# Dandanator_CPC_MX4_v1_2_Rwd.net
KiCad netlist of a schematic drawn in EAGLE
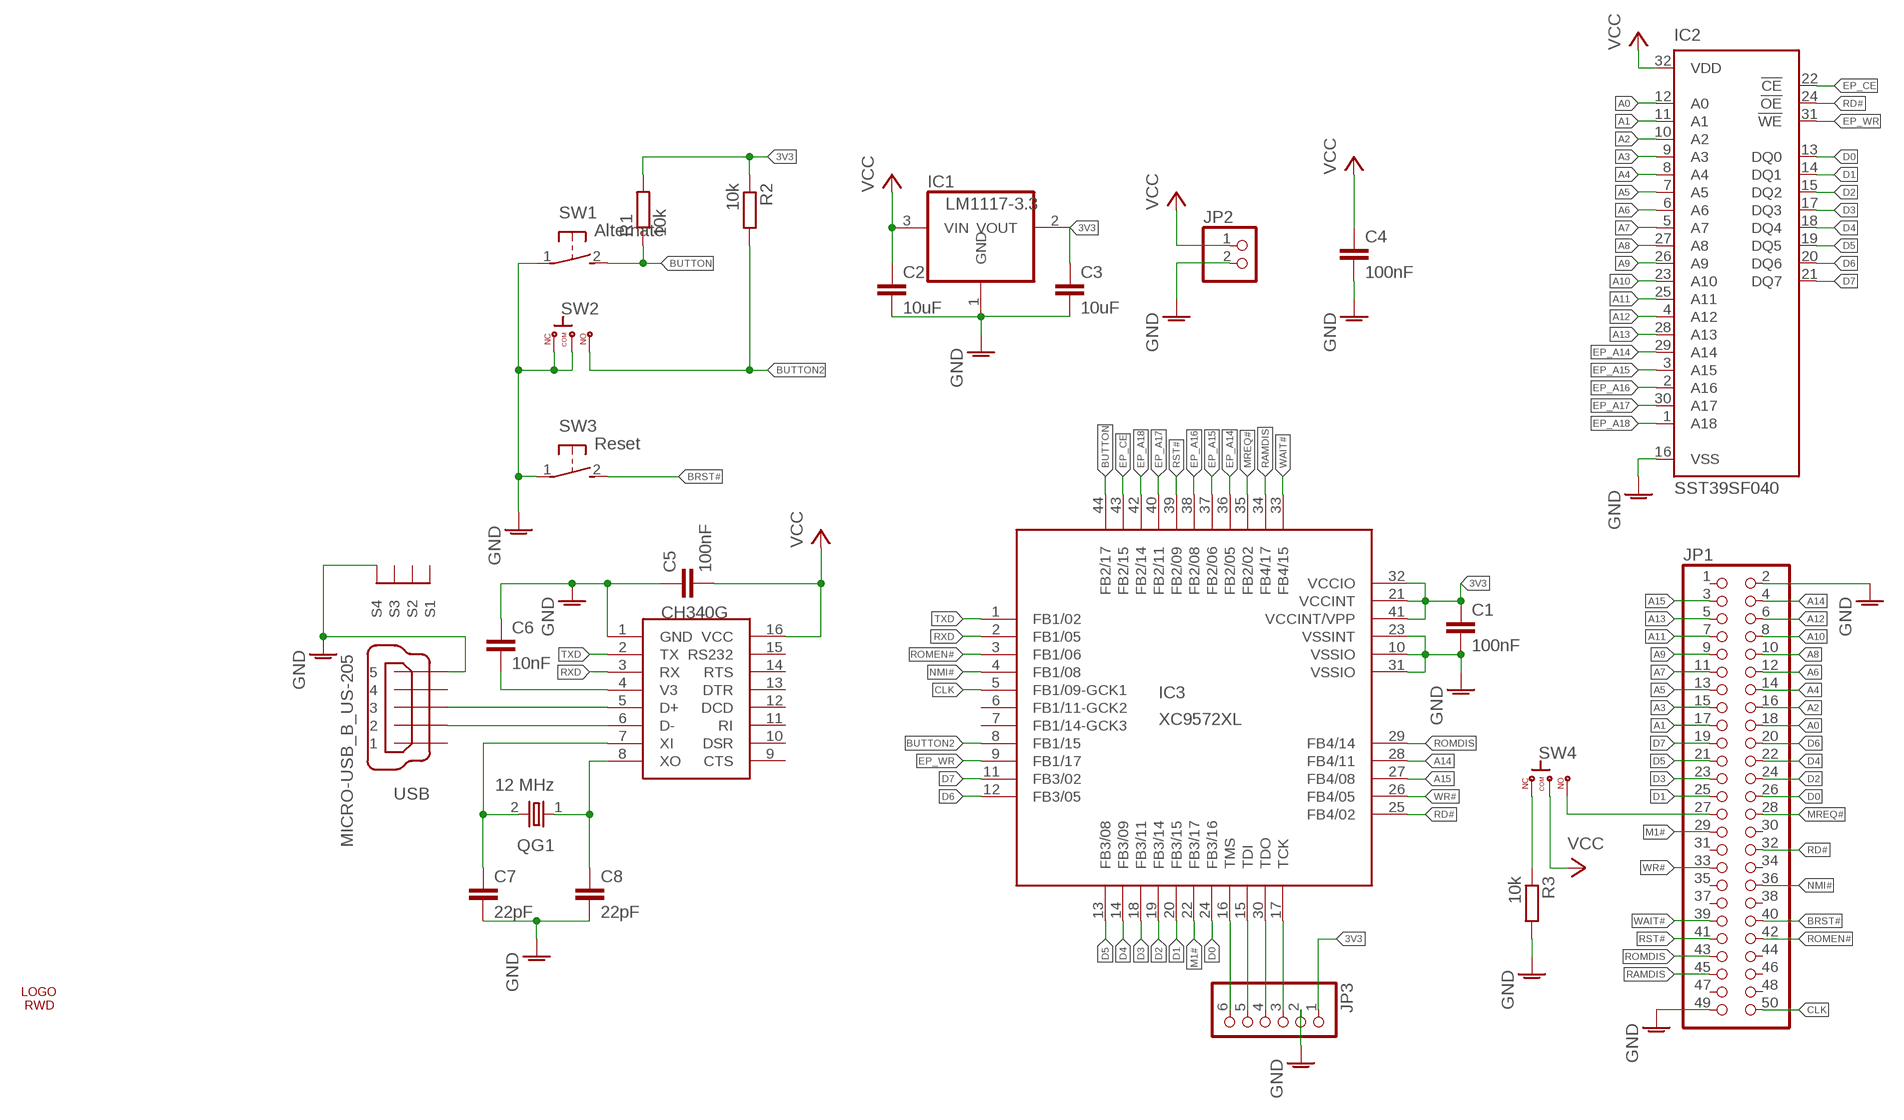
[diagram p0: schematic, sheet 1]

(export (version "E")
  (design (tool "Eeschema 10.0.6"))
  (components
    (comp (ref "C1")
      (value "100nF")
      (footprint "eagle-import:C0805")
      (libsource (lib "eagle-import") (part "C-EUC0805"))
    )
    (comp (ref "C2")
      (value "10uF")
      (footprint "eagle-import:C0805")
      (libsource (lib "eagle-import") (part "C-EUC0805"))
    )
    (comp (ref "C3")
      (value "10uF")
      (footprint "eagle-import:C0805")
      (libsource (lib "eagle-import") (part "C-EUC0805"))
    )
    (comp (ref "C4")
      (value "100nF")
      (footprint "eagle-import:C0805")
      (libsource (lib "eagle-import") (part "C-EUC0805"))
    )
    (comp (ref "C5")
      (value "100nF")
      (footprint "eagle-import:C0805")
      (libsource (lib "eagle-import") (part "C-EUC0805"))
    )
    (comp (ref "C6")
      (value "10nF")
      (footprint "eagle-import:C0805")
      (libsource (lib "eagle-import") (part "C-EUC0805"))
    )
    (comp (ref "C7")
      (value "22pF")
      (footprint "eagle-import:C0805")
      (libsource (lib "eagle-import") (part "C-EUC0805"))
    )
    (comp (ref "C8")
      (value "22pF")
      (footprint "eagle-import:C0805")
      (libsource (lib "eagle-import") (part "C-EUC0805"))
    )
    (comp (ref "CH340G")
      (value "CH340G")
      (footprint "eagle-import:SOIC16")
      (libsource (lib "eagle-import") (part "CH340G"))
    )
    (comp (ref "IC1")
      (value "LM1117-3.3")
      (footprint "eagle-import:SOT223")
      (fields (field (name "MPN") "REG1117"))
      (libsource (lib "eagle-import") (part "REG1117"))
    )
    (comp (ref "IC2")
      (value "SST39SF040")
      (footprint "eagle-import:S32")
      (libsource (lib "eagle-import") (part "MICROCHIP_SST39SF040C"))
    )
    (comp (ref "IC3")
      (value "XC9572XL")
      (footprint "eagle-import:S44")
      (libsource (lib "eagle-import") (part "XC9572XL_44PLCCDIP"))
    )
    (comp (ref "JP1")
      (value "PINHD-2X25")
      (footprint "eagle-import:2X25")
      (libsource (lib "eagle-import") (part "PINHD-2X25"))
    )
    (comp (ref "JP2")
      (value "PINHD-1X2")
      (footprint "eagle-import:1X02")
      (libsource (lib "eagle-import") (part "PINHD-1X2"))
    )
    (comp (ref "JP3")
      (value "PINHD-1X6")
      (footprint "eagle-import:1X06")
      (libsource (lib "eagle-import") (part "PINHD-1X6"))
    )
    (comp (ref "QG1")
      (value "12 MHz")
      (footprint "eagle-import:CRYSTAL_HC49_S")
      (libsource (lib "eagle-import") (part "CRYSTAL_CRYSTALHC49S"))
    )
    (comp (ref "R1")
      (value "10k")
      (footprint "eagle-import:R0805")
      (libsource (lib "eagle-import") (part "R-EU_R0805"))
    )
    (comp (ref "R2")
      (value "10k")
      (footprint "eagle-import:R0805")
      (libsource (lib "eagle-import") (part "R-EU_R0805"))
    )
    (comp (ref "R3")
      (value "10k")
      (footprint "eagle-import:R0805")
      (libsource (lib "eagle-import") (part "R-EU_R0805"))
    )
    (comp (ref "SW1")
      (value "Alternate")
      (footprint "eagle-import:B3F-31XX")
      (fields (field (name "MPN") "B3F-3100"))
      (libsource (lib "eagle-import") (part "31-XX"))
    )
    (comp (ref "SW2")
      (value "Disable")
      (footprint "eagle-import:1P2T-MSK12D19-DIP")
      (libsource (lib "eagle-import") (part "1P2T-MSK12D19"))
    )
    (comp (ref "SW3")
      (value "Reset")
      (footprint "eagle-import:B3F-31XX")
      (fields (field (name "MPN") "B3F-3100"))
      (libsource (lib "eagle-import") (part "31-XX"))
    )
    (comp (ref "SW4")
      (value "ON/OFF")
      (footprint "eagle-import:1P2T-MSK12D19-DIP")
      (libsource (lib "eagle-import") (part "1P2T-MSK12D19"))
    )
    (comp (ref "U$1")
      (value "LOGO7BOTTOM")
      (footprint "eagle-import:LOGO7_SK22")
      (libsource (lib "eagle-import") (part "LOGO7BOTTOM"))
    )
    (comp (ref "USB")
      (value "MICRO-USB_B_US-205")
      (footprint "eagle-import:MICRO-USB_B_US-205_DIP")
      (libsource (lib "eagle-import") (part "MICRO-USB_B_US-205"))
    )
  )
  (nets
    (net (code "1") (name "3V3") (class "Default")
      (node (ref "C1") (pin "1") (pinfunction "1_1") (pintype "passive"))
      (node (ref "C3") (pin "1") (pinfunction "1_1") (pintype "passive"))
      (node (ref "IC1") (pin "2") (pinfunction "VOUT_2") (pintype "output"))
      (node (ref "IC3") (pin "21") (pinfunction "VCCINT_21") (pintype "power_in"))
      (node (ref "IC3") (pin "32") (pinfunction "VCCIO_32") (pintype "power_in"))
      (node (ref "IC3") (pin "41") (pinfunction "VCCINT/VPP_41") (pintype "input"))
      (node (ref "JP3") (pin "1") (pinfunction "1_1") (pintype "passive"))
      (node (ref "R1") (pin "2") (pinfunction "2_2") (pintype "passive"))
      (node (ref "R2") (pin "1") (pinfunction "1_1") (pintype "passive"))
    )
    (net (code "2") (name "A0") (class "Default")
      (node (ref "IC2") (pin "12") (pinfunction "A0_12") (pintype "input"))
      (node (ref "JP1") (pin "18") (pinfunction "18_18") (pintype "passive"))
    )
    (net (code "3") (name "A1") (class "Default")
      (node (ref "IC2") (pin "11") (pinfunction "A1_11") (pintype "input"))
      (node (ref "JP1") (pin "17") (pinfunction "17_17") (pintype "passive"))
    )
    (net (code "4") (name "A2") (class "Default")
      (node (ref "IC2") (pin "10") (pinfunction "A2_10") (pintype "input"))
      (node (ref "JP1") (pin "16") (pinfunction "16_16") (pintype "passive"))
    )
    (net (code "5") (name "A3") (class "Default")
      (node (ref "IC2") (pin "9") (pinfunction "A3_9") (pintype "input"))
      (node (ref "JP1") (pin "15") (pinfunction "15_15") (pintype "passive"))
    )
    (net (code "6") (name "A4") (class "Default")
      (node (ref "IC2") (pin "8") (pinfunction "A4_8") (pintype "input"))
      (node (ref "JP1") (pin "14") (pinfunction "14_14") (pintype "passive"))
    )
    (net (code "7") (name "A5") (class "Default")
      (node (ref "IC2") (pin "7") (pinfunction "A5_7") (pintype "input"))
      (node (ref "JP1") (pin "13") (pinfunction "13_13") (pintype "passive"))
    )
    (net (code "8") (name "A6") (class "Default")
      (node (ref "IC2") (pin "6") (pinfunction "A6_6") (pintype "input"))
      (node (ref "JP1") (pin "12") (pinfunction "12_12") (pintype "passive"))
    )
    (net (code "9") (name "A7") (class "Default")
      (node (ref "IC2") (pin "5") (pinfunction "A7_5") (pintype "input"))
      (node (ref "JP1") (pin "11") (pinfunction "11_11") (pintype "passive"))
    )
    (net (code "10") (name "A8") (class "Default")
      (node (ref "IC2") (pin "27") (pinfunction "A8_27") (pintype "input"))
      (node (ref "JP1") (pin "10") (pinfunction "10_10") (pintype "passive"))
    )
    (net (code "11") (name "A9") (class "Default")
      (node (ref "IC2") (pin "26") (pinfunction "A9_26") (pintype "input"))
      (node (ref "JP1") (pin "9") (pinfunction "9_9") (pintype "passive"))
    )
    (net (code "12") (name "A10") (class "Default")
      (node (ref "IC2") (pin "23") (pinfunction "A10_23") (pintype "input"))
      (node (ref "JP1") (pin "8") (pinfunction "8_8") (pintype "passive"))
    )
    (net (code "13") (name "A11") (class "Default")
      (node (ref "IC2") (pin "25") (pinfunction "A11_25") (pintype "input"))
      (node (ref "JP1") (pin "7") (pinfunction "7_7") (pintype "passive"))
    )
    (net (code "14") (name "A12") (class "Default")
      (node (ref "IC2") (pin "4") (pinfunction "A12_4") (pintype "input"))
      (node (ref "JP1") (pin "6") (pinfunction "6_6") (pintype "passive"))
    )
    (net (code "15") (name "A13") (class "Default")
      (node (ref "IC2") (pin "28") (pinfunction "A13_28") (pintype "input"))
      (node (ref "JP1") (pin "5") (pinfunction "5_5") (pintype "passive"))
    )
    (net (code "16") (name "A14") (class "Default")
      (node (ref "IC3") (pin "28") (pinfunction "FB4/11_28") (pintype "bidirectional"))
      (node (ref "JP1") (pin "4") (pinfunction "4_4") (pintype "passive"))
    )
    (net (code "17") (name "A15") (class "Default")
      (node (ref "IC3") (pin "27") (pinfunction "FB4/08_27") (pintype "bidirectional"))
      (node (ref "JP1") (pin "3") (pinfunction "3_3") (pintype "passive"))
    )
    (net (code "18") (name "BRST#") (class "Default")
      (node (ref "JP1") (pin "40") (pinfunction "40_40") (pintype "passive"))
      (node (ref "SW3") (pin "2") (pinfunction "S_2") (pintype "passive"))
    )
    (net (code "19") (name "BUTTON") (class "Default")
      (node (ref "IC3") (pin "44") (pinfunction "FB2/17_44") (pintype "bidirectional"))
      (node (ref "R1") (pin "1") (pinfunction "1_1") (pintype "passive"))
      (node (ref "SW1") (pin "2") (pinfunction "S_2") (pintype "passive"))
    )
    (net (code "20") (name "BUTTON2") (class "Default")
      (node (ref "IC3") (pin "8") (pinfunction "FB1/15_8") (pintype "bidirectional"))
      (node (ref "R2") (pin "2") (pinfunction "2_2") (pintype "passive"))
      (node (ref "SW2") (pin "P$3") (pinfunction "3_P$3") (pintype "passive"))
    )
    (net (code "21") (name "CLK") (class "Default")
      (node (ref "IC3") (pin "5") (pinfunction "FB1/09-GCK1_5") (pintype "bidirectional"))
      (node (ref "JP1") (pin "50") (pinfunction "50_50") (pintype "passive"))
    )
    (net (code "22") (name "D0") (class "Default")
      (node (ref "IC2") (pin "13") (pinfunction "DQ0_13") (pintype "tri_state"))
      (node (ref "IC3") (pin "24") (pinfunction "FB3/16_24") (pintype "bidirectional"))
      (node (ref "JP1") (pin "26") (pinfunction "26_26") (pintype "passive"))
    )
    (net (code "23") (name "D1") (class "Default")
      (node (ref "IC2") (pin "14") (pinfunction "DQ1_14") (pintype "tri_state"))
      (node (ref "IC3") (pin "20") (pinfunction "FB3/15_20") (pintype "bidirectional"))
      (node (ref "JP1") (pin "25") (pinfunction "25_25") (pintype "passive"))
    )
    (net (code "24") (name "D2") (class "Default")
      (node (ref "IC2") (pin "15") (pinfunction "DQ2_15") (pintype "tri_state"))
      (node (ref "IC3") (pin "19") (pinfunction "FB3/14_19") (pintype "bidirectional"))
      (node (ref "JP1") (pin "24") (pinfunction "24_24") (pintype "passive"))
    )
    (net (code "25") (name "D3") (class "Default")
      (node (ref "IC2") (pin "17") (pinfunction "DQ3_17") (pintype "tri_state"))
      (node (ref "IC3") (pin "18") (pinfunction "FB3/11_18") (pintype "bidirectional"))
      (node (ref "JP1") (pin "23") (pinfunction "23_23") (pintype "passive"))
    )
    (net (code "26") (name "D4") (class "Default")
      (node (ref "IC2") (pin "18") (pinfunction "DQ4_18") (pintype "tri_state"))
      (node (ref "IC3") (pin "14") (pinfunction "FB3/09_14") (pintype "bidirectional"))
      (node (ref "JP1") (pin "22") (pinfunction "22_22") (pintype "passive"))
    )
    (net (code "27") (name "D5") (class "Default")
      (node (ref "IC2") (pin "19") (pinfunction "DQ5_19") (pintype "tri_state"))
      (node (ref "IC3") (pin "13") (pinfunction "FB3/08_13") (pintype "bidirectional"))
      (node (ref "JP1") (pin "21") (pinfunction "21_21") (pintype "passive"))
    )
    (net (code "28") (name "D6") (class "Default")
      (node (ref "IC2") (pin "20") (pinfunction "DQ6_20") (pintype "tri_state"))
      (node (ref "IC3") (pin "12") (pinfunction "FB3/05_12") (pintype "bidirectional"))
      (node (ref "JP1") (pin "20") (pinfunction "20_20") (pintype "passive"))
    )
    (net (code "29") (name "D7") (class "Default")
      (node (ref "IC2") (pin "21") (pinfunction "DQ7_21") (pintype "tri_state"))
      (node (ref "IC3") (pin "11") (pinfunction "FB3/02_11") (pintype "bidirectional"))
      (node (ref "JP1") (pin "19") (pinfunction "19_19") (pintype "passive"))
    )
    (net (code "30") (name "EP_A14") (class "Default")
      (node (ref "IC2") (pin "29") (pinfunction "A14_29") (pintype "input"))
      (node (ref "IC3") (pin "36") (pinfunction "FB2/05_36") (pintype "bidirectional"))
    )
    (net (code "31") (name "EP_A15") (class "Default")
      (node (ref "IC2") (pin "3") (pinfunction "A15_3") (pintype "input"))
      (node (ref "IC3") (pin "37") (pinfunction "FB2/06_37") (pintype "bidirectional"))
    )
    (net (code "32") (name "EP_A16") (class "Default")
      (node (ref "IC2") (pin "2") (pinfunction "A16_2") (pintype "input"))
      (node (ref "IC3") (pin "38") (pinfunction "FB2/08_38") (pintype "bidirectional"))
    )
    (net (code "33") (name "EP_A17") (class "Default")
      (node (ref "IC2") (pin "30") (pinfunction "A17_30") (pintype "input"))
      (node (ref "IC3") (pin "40") (pinfunction "FB2/11_40") (pintype "bidirectional"))
    )
    (net (code "34") (name "EP_A18") (class "Default")
      (node (ref "IC2") (pin "1") (pinfunction "A18_1") (pintype "input"))
      (node (ref "IC3") (pin "42") (pinfunction "FB2/14_42") (pintype "bidirectional"))
    )
    (net (code "35") (name "EP_CE") (class "Default")
      (node (ref "IC2") (pin "22") (pinfunction "~{CE}_22") (pintype "input"))
      (node (ref "IC3") (pin "43") (pinfunction "FB2/15_43") (pintype "bidirectional"))
    )
    (net (code "36") (name "EP_WR") (class "Default")
      (node (ref "IC2") (pin "31") (pinfunction "~{WE}_31") (pintype "input"))
      (node (ref "IC3") (pin "9") (pinfunction "FB1/17_9") (pintype "bidirectional"))
    )
    (net (code "37") (name "GND") (class "Default")
      (node (ref "C1") (pin "2") (pinfunction "2_2") (pintype "passive"))
      (node (ref "C2") (pin "2") (pinfunction "2_2") (pintype "passive"))
      (node (ref "C3") (pin "2") (pinfunction "2_2") (pintype "passive"))
      (node (ref "C4") (pin "2") (pinfunction "2_2") (pintype "passive"))
      (node (ref "C5") (pin "1") (pinfunction "1_1") (pintype "passive"))
      (node (ref "C6") (pin "1") (pinfunction "1_1") (pintype "passive"))
      (node (ref "C7") (pin "2") (pinfunction "2_2") (pintype "passive"))
      (node (ref "C8") (pin "2") (pinfunction "2_2") (pintype "passive"))
      (node (ref "CH340G") (pin "1") (pinfunction "GND_1") (pintype "bidirectional"))
      (node (ref "IC1") (pin "1") (pinfunction "GND_1") (pintype "power_in"))
      (node (ref "IC2") (pin "16") (pinfunction "VSS_16") (pintype "power_in"))
      (node (ref "IC3") (pin "10") (pinfunction "VSSIO_10") (pintype "power_in"))
      (node (ref "IC3") (pin "23") (pinfunction "VSSINT_23") (pintype "power_in"))
      (node (ref "IC3") (pin "31") (pinfunction "VSSIO_31") (pintype "power_in"))
      (node (ref "JP1") (pin "2") (pinfunction "2_2") (pintype "passive"))
      (node (ref "JP1") (pin "49") (pinfunction "49_49") (pintype "passive"))
      (node (ref "JP2") (pin "2") (pinfunction "2_2") (pintype "passive"))
      (node (ref "JP3") (pin "2") (pinfunction "2_2") (pintype "passive"))
      (node (ref "R3") (pin "2") (pinfunction "2_2") (pintype "passive"))
      (node (ref "SW1") (pin "1") (pinfunction "P_1") (pintype "passive"))
      (node (ref "SW2") (pin "P$1") (pinfunction "1_P$1") (pintype "passive"))
      (node (ref "SW2") (pin "P$2") (pinfunction "2_P$2") (pintype "passive"))
      (node (ref "SW3") (pin "1") (pinfunction "P_1") (pintype "passive"))
      (node (ref "USB") (pin "5") (pinfunction "5_5") (pintype "passive"))
      (node (ref "USB") (pin "M4") (pinfunction "S4_M4") (pintype "passive"))
    )
    (net (code "38") (name "M1#") (class "Default")
      (node (ref "IC3") (pin "22") (pinfunction "FB3/17_22") (pintype "bidirectional"))
      (node (ref "JP1") (pin "29") (pinfunction "29_29") (pintype "passive"))
    )
    (net (code "39") (name "MREQ#") (class "Default")
      (node (ref "IC3") (pin "35") (pinfunction "FB2/02_35") (pintype "bidirectional"))
      (node (ref "JP1") (pin "28") (pinfunction "28_28") (pintype "passive"))
    )
    (net (code "40") (name "NMI#") (class "Default")
      (node (ref "IC3") (pin "4") (pinfunction "FB1/08_4") (pintype "bidirectional"))
      (node (ref "JP1") (pin "36") (pinfunction "36_36") (pintype "passive"))
    )
    (net (code "41") (name "Net-(CH340G-D+)") (class "Default")
      (node (ref "CH340G") (pin "5") (pinfunction "D+_5") (pintype "bidirectional"))
      (node (ref "USB") (pin "3") (pinfunction "3_3") (pintype "passive"))
    )
    (net (code "42") (name "Net-(CH340G-D-)") (class "Default")
      (node (ref "CH340G") (pin "6") (pinfunction "D-_6") (pintype "bidirectional"))
      (node (ref "USB") (pin "2") (pinfunction "2_2") (pintype "passive"))
    )
    (net (code "43") (name "Net-(CH340G-V3)") (class "Default")
      (node (ref "C6") (pin "2") (pinfunction "2_2") (pintype "passive"))
      (node (ref "CH340G") (pin "4") (pinfunction "V3_4") (pintype "bidirectional"))
    )
    (net (code "44") (name "Net-(CH340G-XI)") (class "Default")
      (node (ref "C7") (pin "1") (pinfunction "1_1") (pintype "passive"))
      (node (ref "CH340G") (pin "7") (pinfunction "XI_7") (pintype "bidirectional"))
      (node (ref "QG1") (pin "2") (pinfunction "2_2") (pintype "passive"))
    )
    (net (code "45") (name "Net-(CH340G-XO)") (class "Default")
      (node (ref "C8") (pin "1") (pinfunction "1_1") (pintype "passive"))
      (node (ref "CH340G") (pin "8") (pinfunction "XO_8") (pintype "bidirectional"))
      (node (ref "QG1") (pin "1") (pinfunction "1_1") (pintype "passive"))
    )
    (net (code "46") (name "Net-(IC3-TCK)") (class "Default")
      (node (ref "IC3") (pin "17") (pinfunction "TCK_17") (pintype "input"))
      (node (ref "JP3") (pin "3") (pinfunction "3_3") (pintype "passive"))
    )
    (net (code "47") (name "Net-(IC3-TDI)") (class "Default")
      (node (ref "IC3") (pin "15") (pinfunction "TDI_15") (pintype "input"))
      (node (ref "JP3") (pin "5") (pinfunction "5_5") (pintype "passive"))
    )
    (net (code "48") (name "Net-(IC3-TDO)") (class "Default")
      (node (ref "IC3") (pin "30") (pinfunction "TDO_30") (pintype "output"))
      (node (ref "JP3") (pin "4") (pinfunction "4_4") (pintype "passive"))
    )
    (net (code "49") (name "Net-(IC3-TMS)") (class "Default")
      (node (ref "IC3") (pin "16") (pinfunction "TMS_16") (pintype "input"))
      (node (ref "JP3") (pin "6") (pinfunction "6_6") (pintype "passive"))
    )
    (net (code "50") (name "Net-(SW4-1)") (class "Default")
      (node (ref "R3") (pin "1") (pinfunction "1_1") (pintype "passive"))
      (node (ref "SW4") (pin "P$1") (pinfunction "1_P$1") (pintype "passive"))
    )
    (net (code "51") (name "Net-(SW4-3)") (class "Default")
      (node (ref "JP1") (pin "27") (pinfunction "27_27") (pintype "passive"))
      (node (ref "SW4") (pin "P$3") (pinfunction "3_P$3") (pintype "passive"))
    )
    (net (code "52") (name "RAMDIS") (class "Default")
      (node (ref "IC3") (pin "34") (pinfunction "FB4/17_34") (pintype "bidirectional"))
      (node (ref "JP1") (pin "45") (pinfunction "45_45") (pintype "passive"))
    )
    (net (code "53") (name "RD#") (class "Default")
      (node (ref "IC2") (pin "24") (pinfunction "~{OE}_24") (pintype "input"))
      (node (ref "IC3") (pin "25") (pinfunction "FB4/02_25") (pintype "bidirectional"))
      (node (ref "JP1") (pin "32") (pinfunction "32_32") (pintype "passive"))
    )
    (net (code "54") (name "ROMDIS") (class "Default")
      (node (ref "IC3") (pin "29") (pinfunction "FB4/14_29") (pintype "bidirectional"))
      (node (ref "JP1") (pin "43") (pinfunction "43_43") (pintype "passive"))
    )
    (net (code "55") (name "ROMEN#") (class "Default")
      (node (ref "IC3") (pin "3") (pinfunction "FB1/06_3") (pintype "bidirectional"))
      (node (ref "JP1") (pin "42") (pinfunction "42_42") (pintype "passive"))
    )
    (net (code "56") (name "RST#") (class "Default")
      (node (ref "IC3") (pin "39") (pinfunction "FB2/09_39") (pintype "bidirectional"))
      (node (ref "JP1") (pin "41") (pinfunction "41_41") (pintype "passive"))
    )
    (net (code "57") (name "RXD") (class "Default")
      (node (ref "CH340G") (pin "3") (pinfunction "RX_3") (pintype "bidirectional"))
      (node (ref "IC3") (pin "2") (pinfunction "FB1/05_2") (pintype "bidirectional"))
    )
    (net (code "58") (name "TXD") (class "Default")
      (node (ref "CH340G") (pin "2") (pinfunction "TX_2") (pintype "bidirectional"))
      (node (ref "IC3") (pin "1") (pinfunction "FB1/02_1") (pintype "bidirectional"))
    )
    (net (code "59") (name "VCC") (class "Default")
      (node (ref "C2") (pin "1") (pinfunction "1_1") (pintype "passive"))
      (node (ref "C4") (pin "1") (pinfunction "1_1") (pintype "passive"))
      (node (ref "C5") (pin "2") (pinfunction "2_2") (pintype "passive"))
      (node (ref "CH340G") (pin "16") (pinfunction "VCC_16") (pintype "bidirectional"))
      (node (ref "IC1") (pin "3") (pinfunction "VIN_3") (pintype "input"))
      (node (ref "IC2") (pin "32") (pinfunction "VDD_32") (pintype "power_in"))
      (node (ref "JP2") (pin "1") (pinfunction "1_1") (pintype "passive"))
      (node (ref "SW4") (pin "P$2") (pinfunction "2_P$2") (pintype "passive"))
    )
    (net (code "60") (name "WAIT#") (class "Default")
      (node (ref "IC3") (pin "33") (pinfunction "FB4/15_33") (pintype "bidirectional"))
      (node (ref "JP1") (pin "39") (pinfunction "39_39") (pintype "passive"))
    )
    (net (code "61") (name "WR#") (class "Default")
      (node (ref "IC3") (pin "26") (pinfunction "FB4/05_26") (pintype "bidirectional"))
      (node (ref "JP1") (pin "33") (pinfunction "33_33") (pintype "passive"))
    )
    (net (code "62") (name "unconnected-(CH340G-CTS-Pad9)") (class "Default")
      (node (ref "CH340G") (pin "9") (pinfunction "CTS_9") (pintype "bidirectional"))
    )
    (net (code "63") (name "unconnected-(CH340G-DCD-Pad12)") (class "Default")
      (node (ref "CH340G") (pin "12") (pinfunction "DCD_12") (pintype "bidirectional"))
    )
    (net (code "64") (name "unconnected-(CH340G-DSR-Pad10)") (class "Default")
      (node (ref "CH340G") (pin "10") (pinfunction "DSR_10") (pintype "bidirectional"))
    )
    (net (code "65") (name "unconnected-(CH340G-DTR-Pad13)") (class "Default")
      (node (ref "CH340G") (pin "13") (pinfunction "DTR_13") (pintype "bidirectional"))
    )
    (net (code "66") (name "unconnected-(CH340G-RI-Pad11)") (class "Default")
      (node (ref "CH340G") (pin "11") (pinfunction "RI_11") (pintype "bidirectional"))
    )
    (net (code "67") (name "unconnected-(CH340G-RS232-Pad15)") (class "Default")
      (node (ref "CH340G") (pin "15") (pinfunction "RS232_15") (pintype "bidirectional"))
    )
    (net (code "68") (name "unconnected-(CH340G-RTS-Pad14)") (class "Default")
      (node (ref "CH340G") (pin "14") (pinfunction "RTS_14") (pintype "bidirectional"))
    )
    (net (code "69") (name "unconnected-(IC3-FB1{slash}11-GCK2-Pad6)") (class "Default")
      (node (ref "IC3") (pin "6") (pinfunction "FB1/11-GCK2_6") (pintype "bidirectional"))
    )
    (net (code "70") (name "unconnected-(IC3-FB1{slash}14-GCK3-Pad7)") (class "Default")
      (node (ref "IC3") (pin "7") (pinfunction "FB1/14-GCK3_7") (pintype "bidirectional"))
    )
    (net (code "71") (name "unconnected-(JP1-Pad1)") (class "Default")
      (node (ref "JP1") (pin "1") (pinfunction "1_1") (pintype "passive"))
    )
    (net (code "72") (name "unconnected-(JP1-Pad30)") (class "Default")
      (node (ref "JP1") (pin "30") (pinfunction "30_30") (pintype "passive"))
    )
    (net (code "73") (name "unconnected-(JP1-Pad31)") (class "Default")
      (node (ref "JP1") (pin "31") (pinfunction "31_31") (pintype "passive"))
    )
    (net (code "74") (name "unconnected-(JP1-Pad34)") (class "Default")
      (node (ref "JP1") (pin "34") (pinfunction "34_34") (pintype "passive"))
    )
    (net (code "75") (name "unconnected-(JP1-Pad35)") (class "Default")
      (node (ref "JP1") (pin "35") (pinfunction "35_35") (pintype "passive"))
    )
    (net (code "76") (name "unconnected-(JP1-Pad37)") (class "Default")
      (node (ref "JP1") (pin "37") (pinfunction "37_37") (pintype "passive"))
    )
    (net (code "77") (name "unconnected-(JP1-Pad38)") (class "Default")
      (node (ref "JP1") (pin "38") (pinfunction "38_38") (pintype "passive"))
    )
    (net (code "78") (name "unconnected-(JP1-Pad44)") (class "Default")
      (node (ref "JP1") (pin "44") (pinfunction "44_44") (pintype "passive"))
    )
    (net (code "79") (name "unconnected-(JP1-Pad46)") (class "Default")
      (node (ref "JP1") (pin "46") (pinfunction "46_46") (pintype "passive"))
    )
    (net (code "80") (name "unconnected-(JP1-Pad47)") (class "Default")
      (node (ref "JP1") (pin "47") (pinfunction "47_47") (pintype "passive"))
    )
    (net (code "81") (name "unconnected-(JP1-Pad48)") (class "Default")
      (node (ref "JP1") (pin "48") (pinfunction "48_48") (pintype "passive"))
    )
    (net (code "82") (name "unconnected-(USB-Pad1)") (class "Default")
      (node (ref "USB") (pin "1") (pinfunction "1_1") (pintype "passive"))
    )
    (net (code "83") (name "unconnected-(USB-Pad4)") (class "Default")
      (node (ref "USB") (pin "4") (pinfunction "4_4") (pintype "passive"))
    )
    (net (code "84") (name "unconnected-(USB-S1-PadM1)") (class "Default")
      (node (ref "USB") (pin "M1") (pinfunction "S1_M1") (pintype "passive"))
    )
    (net (code "85") (name "unconnected-(USB-S2-PadM2)") (class "Default")
      (node (ref "USB") (pin "M2") (pinfunction "S2_M2") (pintype "passive"))
    )
    (net (code "86") (name "unconnected-(USB-S3-PadM3)") (class "Default")
      (node (ref "USB") (pin "M3") (pinfunction "S3_M3") (pintype "passive"))
    )
  )
)
